# CAM_CONNECTOR.net
KiCad netlist of a schematic drawn in Altium Designer
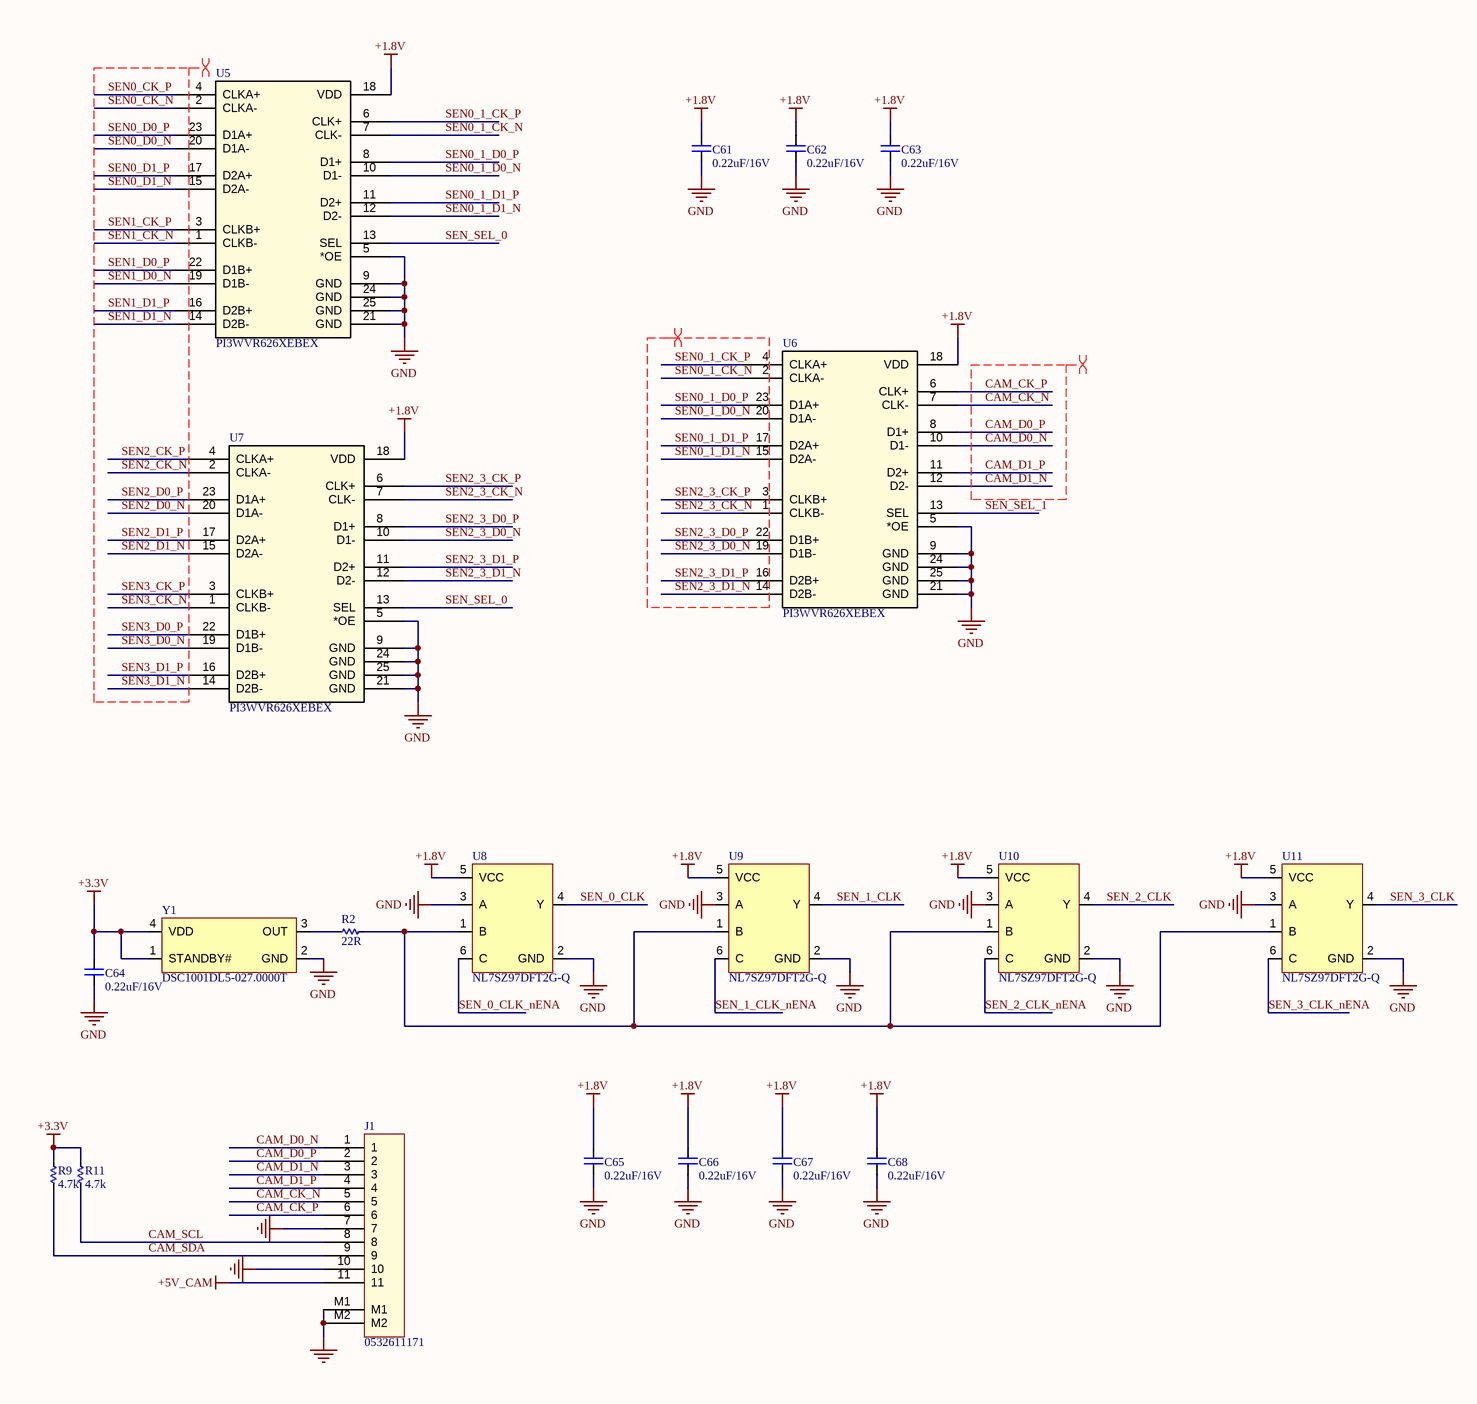
[diagram p0: CAM_CONNECTOR.SchDoc]

(export (version "E")
  (design (tool "Eeschema 10.0.6"))
  (components
    (comp (ref "C61")
      (value "0.22uF/16V")
      (footprint "CAP_C_1005X60")
      (description "CAP_Chip")
      (libsource (lib "LABLIB") (part "CAP_SMD"))
    )
    (comp (ref "C62")
      (value "0.22uF/16V")
      (footprint "CAP_C_1005X60")
      (description "CAP_Chip")
      (libsource (lib "LABLIB") (part "CAP_SMD"))
    )
    (comp (ref "C63")
      (value "0.22uF/16V")
      (footprint "CAP_C_1005X60")
      (description "CAP_Chip")
      (libsource (lib "LABLIB") (part "CAP_SMD"))
    )
    (comp (ref "C64")
      (value "0.22uF/16V")
      (footprint "CAP_C_1005X60")
      (description "CAP_Chip")
      (libsource (lib "LABLIB") (part "CAP_SMD"))
    )
    (comp (ref "C65")
      (value "0.22uF/16V")
      (footprint "CAP_C_1005X60")
      (description "CAP_Chip")
      (libsource (lib "LABLIB") (part "CAP_SMD"))
    )
    (comp (ref "C66")
      (value "0.22uF/16V")
      (footprint "CAP_C_1005X60")
      (description "CAP_Chip")
      (libsource (lib "LABLIB") (part "CAP_SMD"))
    )
    (comp (ref "C67")
      (value "0.22uF/16V")
      (footprint "CAP_C_1005X60")
      (description "CAP_Chip")
      (libsource (lib "LABLIB") (part "CAP_SMD"))
    )
    (comp (ref "C68")
      (value "0.22uF/16V")
      (footprint "CAP_C_1005X60")
      (description "CAP_Chip")
      (libsource (lib "LABLIB") (part "CAP_SMD"))
    )
    (comp (ref "J1")
      (value "0532611171")
      (footprint "MOLEX_0532611171")
      (libsource (lib "LABLIB") (part "Header 11x1_2M"))
    )
    (comp (ref "R2")
      (value "22R")
      (footprint "RES_C_1005X40")
      (description "RES-Chip")
      (fields
        (field (name "MANUFACTURER") "Generic Components")
        (field (name "PUBLISHER") "Altium Hobart Technology Centre")
      )
      (libsource (lib "LABLIB") (part "RES-SMD"))
    )
    (comp (ref "R9")
      (value "4.7k")
      (footprint "RES_C_1005X40")
      (description "RES")
      (libsource (lib "LABLIB") (part "_RES_B_2"))
    )
    (comp (ref "R11")
      (value "4.7k")
      (footprint "RES_C_1005X40")
      (description "RES")
      (libsource (lib "LABLIB") (part "_RES_B_2"))
    )
    (comp (ref "U5")
      (value "PI3WVR626XEBEX")
      (footprint "PI3WVR626XEBEX_DIO_2")
      (libsource (lib "CAMERA_SchLib") (part "PI3WVR626XEBEX"))
    )
    (comp (ref "U6")
      (value "PI3WVR626XEBEX")
      (footprint "PI3WVR626XEBEX_DIO_2")
      (libsource (lib "CAMERA_SchLib") (part "PI3WVR626XEBEX"))
    )
    (comp (ref "U7")
      (value "PI3WVR626XEBEX")
      (footprint "PI3WVR626XEBEX_DIO_2")
      (libsource (lib "CAMERA_SchLib") (part "PI3WVR626XEBEX"))
    )
    (comp (ref "U8")
      (value "NL7SZ97DFT2G-Q")
      (footprint "SC-88")
      (libsource (lib "CAMERA_SchLib") (part "IC_FLEXLOGIC_NL7SZ97DFT2G-Q"))
    )
    (comp (ref "U9")
      (value "NL7SZ97DFT2G-Q")
      (footprint "SC-88")
      (libsource (lib "CAMERA_SchLib") (part "IC_FLEXLOGIC_NL7SZ97DFT2G-Q"))
    )
    (comp (ref "U10")
      (value "NL7SZ97DFT2G-Q")
      (footprint "SC-88")
      (libsource (lib "CAMERA_SchLib") (part "IC_FLEXLOGIC_NL7SZ97DFT2G-Q"))
    )
    (comp (ref "U11")
      (value "NL7SZ97DFT2G-Q")
      (footprint "SC-88")
      (libsource (lib "CAMERA_SchLib") (part "IC_FLEXLOGIC_NL7SZ97DFT2G-Q"))
    )
    (comp (ref "Y1")
      (value "DSC1001DL5-027.0000T")
      (footprint "OSCDFN250X200X89-4N")
      (libsource (lib "CAMERA_SchLib") (part "Y_OSC27MHz_DSC1001DL5-027.0000T"))
    )
  )
  (nets
    (net (code "1") (name "+1.8V") (class "Default")
      (node (ref "C61") (pin "2") (pinfunction "2_2") (pintype "passive"))
      (node (ref "C62") (pin "2") (pinfunction "2_2") (pintype "passive"))
      (node (ref "C63") (pin "2") (pinfunction "2_2") (pintype "passive"))
      (node (ref "C65") (pin "2") (pinfunction "2_2") (pintype "passive"))
      (node (ref "C66") (pin "2") (pinfunction "2_2") (pintype "passive"))
      (node (ref "C67") (pin "2") (pinfunction "2_2") (pintype "passive"))
      (node (ref "C68") (pin "2") (pinfunction "2_2") (pintype "passive"))
      (node (ref "U10") (pin "5") (pinfunction "VCC_5") (pintype "passive"))
      (node (ref "U11") (pin "5") (pinfunction "VCC_5") (pintype "passive"))
      (node (ref "U5") (pin "18") (pinfunction "VDD_18") (pintype "passive"))
      (node (ref "U6") (pin "18") (pinfunction "VDD_18") (pintype "passive"))
      (node (ref "U7") (pin "18") (pinfunction "VDD_18") (pintype "passive"))
      (node (ref "U8") (pin "5") (pinfunction "VCC_5") (pintype "passive"))
      (node (ref "U9") (pin "5") (pinfunction "VCC_5") (pintype "passive"))
    )
    (net (code "2") (name "+3.3V") (class "Default")
      (node (ref "C64") (pin "2") (pinfunction "2_2") (pintype "passive"))
      (node (ref "R11") (pin "1") (pinfunction "1_1") (pintype "passive"))
      (node (ref "R9") (pin "1") (pinfunction "1_1") (pintype "passive"))
      (node (ref "Y1") (pin "1") (pinfunction "STANDBY#_1") (pintype "passive"))
      (node (ref "Y1") (pin "4") (pinfunction "VDD_4") (pintype "passive"))
    )
    (net (code "3") (name "+5V_CAM") (class "Default")
      (node (ref "J1") (pin "11") (pinfunction "11_11") (pintype "passive"))
    )
    (net (code "4") (name "/CAM_CK_N") (class "Default")
      (node (ref "J1") (pin "5") (pinfunction "5_5") (pintype "passive"))
      (node (ref "U6") (pin "7") (pinfunction "CLK-_7") (pintype "passive"))
    )
    (net (code "5") (name "/CAM_CK_P") (class "Default")
      (node (ref "J1") (pin "6") (pinfunction "6_6") (pintype "passive"))
      (node (ref "U6") (pin "6") (pinfunction "CLK+_6") (pintype "passive"))
    )
    (net (code "6") (name "/CAM_D0_N") (class "Default")
      (node (ref "J1") (pin "1") (pinfunction "1_1") (pintype "passive"))
      (node (ref "U6") (pin "10") (pinfunction "D1-_10") (pintype "passive"))
    )
    (net (code "7") (name "/CAM_D0_P") (class "Default")
      (node (ref "J1") (pin "2") (pinfunction "2_2") (pintype "passive"))
      (node (ref "U6") (pin "8") (pinfunction "D1+_8") (pintype "passive"))
    )
    (net (code "8") (name "/CAM_D1_N") (class "Default")
      (node (ref "J1") (pin "3") (pinfunction "3_3") (pintype "passive"))
      (node (ref "U6") (pin "12") (pinfunction "D2-_12") (pintype "passive"))
    )
    (net (code "9") (name "/CAM_D1_P") (class "Default")
      (node (ref "J1") (pin "4") (pinfunction "4_4") (pintype "passive"))
      (node (ref "U6") (pin "11") (pinfunction "D2+_11") (pintype "passive"))
    )
    (net (code "10") (name "/CAM_SCL") (class "Default")
      (node (ref "J1") (pin "8") (pinfunction "8_8") (pintype "passive"))
      (node (ref "R11") (pin "2") (pinfunction "2_2") (pintype "passive"))
    )
    (net (code "11") (name "/CAM_SDA") (class "Default")
      (node (ref "J1") (pin "9") (pinfunction "9_9") (pintype "passive"))
      (node (ref "R9") (pin "2") (pinfunction "2_2") (pintype "passive"))
    )
    (net (code "12") (name "/SEN0_1_CK_N") (class "Default")
      (node (ref "U5") (pin "7") (pinfunction "CLK-_7") (pintype "passive"))
      (node (ref "U6") (pin "2") (pinfunction "CLKA-_2") (pintype "passive"))
    )
    (net (code "13") (name "/SEN0_1_CK_P") (class "Default")
      (node (ref "U5") (pin "6") (pinfunction "CLK+_6") (pintype "passive"))
      (node (ref "U6") (pin "4") (pinfunction "CLKA+_4") (pintype "passive"))
    )
    (net (code "14") (name "/SEN0_1_D0_N") (class "Default")
      (node (ref "U5") (pin "10") (pinfunction "D1-_10") (pintype "passive"))
      (node (ref "U6") (pin "20") (pinfunction "D1A-_20") (pintype "passive"))
    )
    (net (code "15") (name "/SEN0_1_D0_P") (class "Default")
      (node (ref "U5") (pin "8") (pinfunction "D1+_8") (pintype "passive"))
      (node (ref "U6") (pin "23") (pinfunction "D1A+_23") (pintype "passive"))
    )
    (net (code "16") (name "/SEN0_1_D1_N") (class "Default")
      (node (ref "U5") (pin "12") (pinfunction "D2-_12") (pintype "passive"))
      (node (ref "U6") (pin "15") (pinfunction "D2A-_15") (pintype "passive"))
    )
    (net (code "17") (name "/SEN0_1_D1_P") (class "Default")
      (node (ref "U5") (pin "11") (pinfunction "D2+_11") (pintype "passive"))
      (node (ref "U6") (pin "17") (pinfunction "D2A+_17") (pintype "passive"))
    )
    (net (code "18") (name "/SEN0_CK_N") (class "Default")
      (node (ref "U5") (pin "2") (pinfunction "CLKA-_2") (pintype "passive"))
    )
    (net (code "19") (name "/SEN0_CK_P") (class "Default")
      (node (ref "U5") (pin "4") (pinfunction "CLKA+_4") (pintype "passive"))
    )
    (net (code "20") (name "/SEN0_D0_N") (class "Default")
      (node (ref "U5") (pin "20") (pinfunction "D1A-_20") (pintype "passive"))
    )
    (net (code "21") (name "/SEN0_D0_P") (class "Default")
      (node (ref "U5") (pin "23") (pinfunction "D1A+_23") (pintype "passive"))
    )
    (net (code "22") (name "/SEN0_D1_N") (class "Default")
      (node (ref "U5") (pin "15") (pinfunction "D2A-_15") (pintype "passive"))
    )
    (net (code "23") (name "/SEN0_D1_P") (class "Default")
      (node (ref "U5") (pin "17") (pinfunction "D2A+_17") (pintype "passive"))
    )
    (net (code "24") (name "/SEN1_CK_N") (class "Default")
      (node (ref "U5") (pin "1") (pinfunction "CLKB-_1") (pintype "passive"))
    )
    (net (code "25") (name "/SEN1_CK_P") (class "Default")
      (node (ref "U5") (pin "3") (pinfunction "CLKB+_3") (pintype "passive"))
    )
    (net (code "26") (name "/SEN1_D0_N") (class "Default")
      (node (ref "U5") (pin "19") (pinfunction "D1B-_19") (pintype "passive"))
    )
    (net (code "27") (name "/SEN1_D0_P") (class "Default")
      (node (ref "U5") (pin "22") (pinfunction "D1B+_22") (pintype "passive"))
    )
    (net (code "28") (name "/SEN1_D1_N") (class "Default")
      (node (ref "U5") (pin "14") (pinfunction "D2B-_14") (pintype "passive"))
    )
    (net (code "29") (name "/SEN1_D1_P") (class "Default")
      (node (ref "U5") (pin "16") (pinfunction "D2B+_16") (pintype "passive"))
    )
    (net (code "30") (name "/SEN2_3_CK_N") (class "Default")
      (node (ref "U6") (pin "1") (pinfunction "CLKB-_1") (pintype "passive"))
      (node (ref "U7") (pin "7") (pinfunction "CLK-_7") (pintype "passive"))
    )
    (net (code "31") (name "/SEN2_3_CK_P") (class "Default")
      (node (ref "U6") (pin "3") (pinfunction "CLKB+_3") (pintype "passive"))
      (node (ref "U7") (pin "6") (pinfunction "CLK+_6") (pintype "passive"))
    )
    (net (code "32") (name "/SEN2_3_D0_N") (class "Default")
      (node (ref "U6") (pin "19") (pinfunction "D1B-_19") (pintype "passive"))
      (node (ref "U7") (pin "10") (pinfunction "D1-_10") (pintype "passive"))
    )
    (net (code "33") (name "/SEN2_3_D0_P") (class "Default")
      (node (ref "U6") (pin "22") (pinfunction "D1B+_22") (pintype "passive"))
      (node (ref "U7") (pin "8") (pinfunction "D1+_8") (pintype "passive"))
    )
    (net (code "34") (name "/SEN2_3_D1_N") (class "Default")
      (node (ref "U6") (pin "14") (pinfunction "D2B-_14") (pintype "passive"))
      (node (ref "U7") (pin "12") (pinfunction "D2-_12") (pintype "passive"))
    )
    (net (code "35") (name "/SEN2_3_D1_P") (class "Default")
      (node (ref "U6") (pin "16") (pinfunction "D2B+_16") (pintype "passive"))
      (node (ref "U7") (pin "11") (pinfunction "D2+_11") (pintype "passive"))
    )
    (net (code "36") (name "/SEN2_CK_N") (class "Default")
      (node (ref "U7") (pin "2") (pinfunction "CLKA-_2") (pintype "passive"))
    )
    (net (code "37") (name "/SEN2_CK_P") (class "Default")
      (node (ref "U7") (pin "4") (pinfunction "CLKA+_4") (pintype "passive"))
    )
    (net (code "38") (name "/SEN2_D0_N") (class "Default")
      (node (ref "U7") (pin "20") (pinfunction "D1A-_20") (pintype "passive"))
    )
    (net (code "39") (name "/SEN2_D0_P") (class "Default")
      (node (ref "U7") (pin "23") (pinfunction "D1A+_23") (pintype "passive"))
    )
    (net (code "40") (name "/SEN2_D1_N") (class "Default")
      (node (ref "U7") (pin "15") (pinfunction "D2A-_15") (pintype "passive"))
    )
    (net (code "41") (name "/SEN2_D1_P") (class "Default")
      (node (ref "U7") (pin "17") (pinfunction "D2A+_17") (pintype "passive"))
    )
    (net (code "42") (name "/SEN3_CK_N") (class "Default")
      (node (ref "U7") (pin "1") (pinfunction "CLKB-_1") (pintype "passive"))
    )
    (net (code "43") (name "/SEN3_CK_P") (class "Default")
      (node (ref "U7") (pin "3") (pinfunction "CLKB+_3") (pintype "passive"))
    )
    (net (code "44") (name "/SEN3_D0_N") (class "Default")
      (node (ref "U7") (pin "19") (pinfunction "D1B-_19") (pintype "passive"))
    )
    (net (code "45") (name "/SEN3_D0_P") (class "Default")
      (node (ref "U7") (pin "22") (pinfunction "D1B+_22") (pintype "passive"))
    )
    (net (code "46") (name "/SEN3_D1_N") (class "Default")
      (node (ref "U7") (pin "14") (pinfunction "D2B-_14") (pintype "passive"))
    )
    (net (code "47") (name "/SEN3_D1_P") (class "Default")
      (node (ref "U7") (pin "16") (pinfunction "D2B+_16") (pintype "passive"))
    )
    (net (code "48") (name "/SEN_0_CLK") (class "Default")
      (node (ref "U8") (pin "4") (pinfunction "Y_4") (pintype "passive"))
    )
    (net (code "49") (name "/SEN_0_CLK_nENA") (class "Default")
      (node (ref "U8") (pin "6") (pinfunction "C_6") (pintype "passive"))
    )
    (net (code "50") (name "/SEN_1_CLK") (class "Default")
      (node (ref "U9") (pin "4") (pinfunction "Y_4") (pintype "passive"))
    )
    (net (code "51") (name "/SEN_1_CLK_nENA") (class "Default")
      (node (ref "U9") (pin "6") (pinfunction "C_6") (pintype "passive"))
    )
    (net (code "52") (name "/SEN_2_CLK") (class "Default")
      (node (ref "U10") (pin "4") (pinfunction "Y_4") (pintype "passive"))
    )
    (net (code "53") (name "/SEN_2_CLK_nENA") (class "Default")
      (node (ref "U10") (pin "6") (pinfunction "C_6") (pintype "passive"))
    )
    (net (code "54") (name "/SEN_3_CLK") (class "Default")
      (node (ref "U11") (pin "4") (pinfunction "Y_4") (pintype "passive"))
    )
    (net (code "55") (name "/SEN_3_CLK_nENA") (class "Default")
      (node (ref "U11") (pin "6") (pinfunction "C_6") (pintype "passive"))
    )
    (net (code "56") (name "/SEN_SEL_0") (class "Default")
      (node (ref "U5") (pin "13") (pinfunction "SEL_13") (pintype "passive"))
      (node (ref "U7") (pin "13") (pinfunction "SEL_13") (pintype "passive"))
    )
    (net (code "57") (name "/SEN_SEL_1") (class "Default")
      (node (ref "U6") (pin "13") (pinfunction "SEL_13") (pintype "passive"))
    )
    (net (code "58") (name "GND") (class "Default")
      (node (ref "C61") (pin "1") (pinfunction "1_1") (pintype "passive"))
      (node (ref "C62") (pin "1") (pinfunction "1_1") (pintype "passive"))
      (node (ref "C63") (pin "1") (pinfunction "1_1") (pintype "passive"))
      (node (ref "C64") (pin "1") (pinfunction "1_1") (pintype "passive"))
      (node (ref "C65") (pin "1") (pinfunction "1_1") (pintype "passive"))
      (node (ref "C66") (pin "1") (pinfunction "1_1") (pintype "passive"))
      (node (ref "C67") (pin "1") (pinfunction "1_1") (pintype "passive"))
      (node (ref "C68") (pin "1") (pinfunction "1_1") (pintype "passive"))
      (node (ref "J1") (pin "10") (pinfunction "10_10") (pintype "passive"))
      (node (ref "J1") (pin "7") (pinfunction "7_7") (pintype "passive"))
      (node (ref "J1") (pin "M1") (pinfunction "M1_M1") (pintype "passive"))
      (node (ref "J1") (pin "M2") (pinfunction "M2_M2") (pintype "passive"))
      (node (ref "U10") (pin "2") (pinfunction "GND_2") (pintype "passive"))
      (node (ref "U10") (pin "3") (pinfunction "A_3") (pintype "passive"))
      (node (ref "U11") (pin "2") (pinfunction "GND_2") (pintype "passive"))
      (node (ref "U11") (pin "3") (pinfunction "A_3") (pintype "passive"))
      (node (ref "U5") (pin "21") (pinfunction "GND_21") (pintype "passive"))
      (node (ref "U5") (pin "24") (pinfunction "GND_24") (pintype "passive"))
      (node (ref "U5") (pin "25") (pinfunction "GND_25") (pintype "passive"))
      (node (ref "U5") (pin "5") (pinfunction "*OE_5") (pintype "passive"))
      (node (ref "U5") (pin "9") (pinfunction "GND_9") (pintype "passive"))
      (node (ref "U6") (pin "21") (pinfunction "GND_21") (pintype "passive"))
      (node (ref "U6") (pin "24") (pinfunction "GND_24") (pintype "passive"))
      (node (ref "U6") (pin "25") (pinfunction "GND_25") (pintype "passive"))
      (node (ref "U6") (pin "5") (pinfunction "*OE_5") (pintype "passive"))
      (node (ref "U6") (pin "9") (pinfunction "GND_9") (pintype "passive"))
      (node (ref "U7") (pin "21") (pinfunction "GND_21") (pintype "passive"))
      (node (ref "U7") (pin "24") (pinfunction "GND_24") (pintype "passive"))
      (node (ref "U7") (pin "25") (pinfunction "GND_25") (pintype "passive"))
      (node (ref "U7") (pin "5") (pinfunction "*OE_5") (pintype "passive"))
      (node (ref "U7") (pin "9") (pinfunction "GND_9") (pintype "passive"))
      (node (ref "U8") (pin "2") (pinfunction "GND_2") (pintype "passive"))
      (node (ref "U8") (pin "3") (pinfunction "A_3") (pintype "passive"))
      (node (ref "U9") (pin "2") (pinfunction "GND_2") (pintype "passive"))
      (node (ref "U9") (pin "3") (pinfunction "A_3") (pintype "passive"))
      (node (ref "Y1") (pin "2") (pinfunction "GND_2") (pintype "passive"))
    )
    (net (code "59") (name "Net-(U10-B)") (class "Default")
      (node (ref "R2") (pin "1") (pinfunction "1_1") (pintype "passive"))
      (node (ref "U10") (pin "1") (pinfunction "B_1") (pintype "passive"))
      (node (ref "U11") (pin "1") (pinfunction "B_1") (pintype "passive"))
      (node (ref "U8") (pin "1") (pinfunction "B_1") (pintype "passive"))
      (node (ref "U9") (pin "1") (pinfunction "B_1") (pintype "passive"))
    )
    (net (code "60") (name "Net-(Y1-OUT)") (class "Default")
      (node (ref "R2") (pin "2") (pinfunction "2_2") (pintype "passive"))
      (node (ref "Y1") (pin "3") (pinfunction "OUT_3") (pintype "passive"))
    )
  )
)
